# BigTime.net
KiCad netlist of a schematic drawn in EAGLE
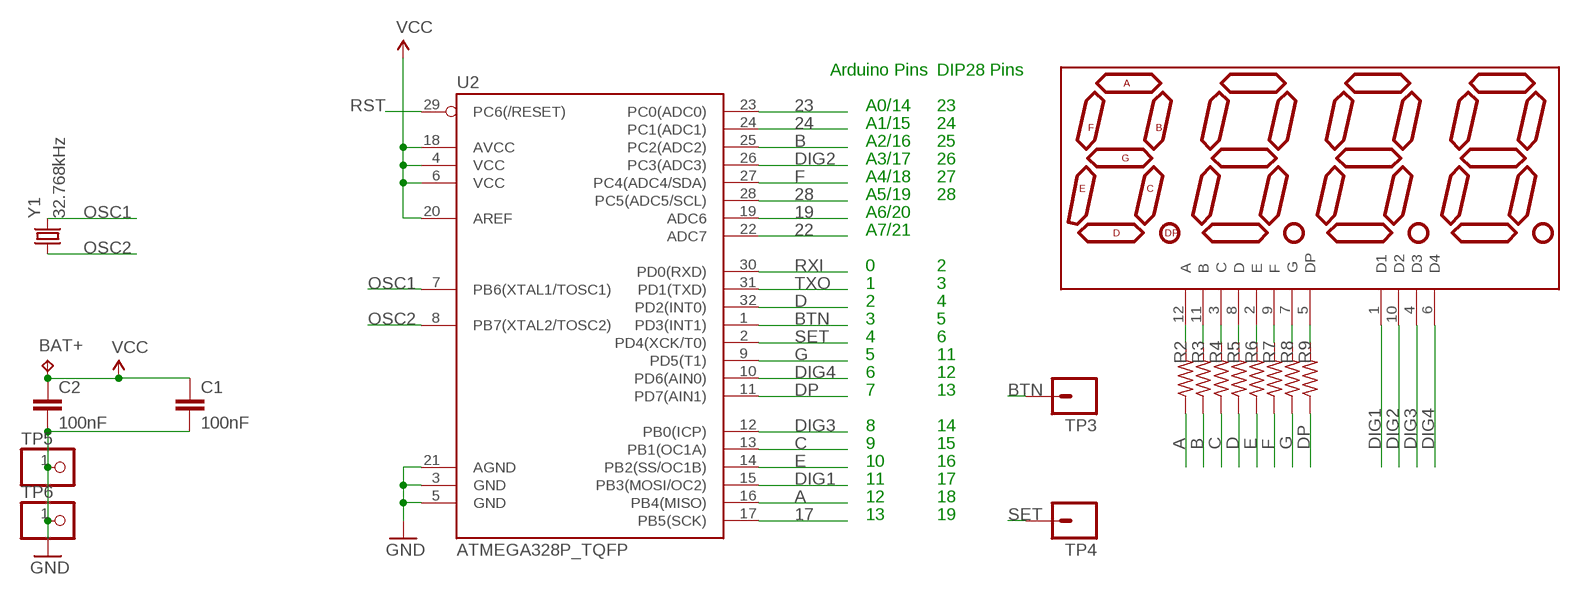
[diagram p0: schematic, sheet 1]

(export (version "E")
  (design (tool "Eeschema 10.0.6"))
  (components
    (comp (ref "BAT+")
      (value "TPTP20R")
      (footprint "eagle-import:TP20R")
      (libsource (lib "eagle-import") (part "TPTP20R"))
    )
    (comp (ref "C1")
      (value "100nF")
      (footprint "eagle-import:C0805")
      (libsource (lib "eagle-import") (part "C-EUC0805"))
    )
    (comp (ref "C2")
      (value "100nF")
      (footprint "eagle-import:C0805")
      (libsource (lib "eagle-import") (part "C-EUC0805"))
    )
    (comp (ref "DISP1")
      (value "7-SEGMENT-4DIGIT-COUNTER-HP-BUBBLE-SM")
      (footprint "eagle-import:DIL12_SM")
      (libsource (lib "eagle-import") (part "7-SEGMENT-4DIGIT-COUNTER-HP-BUBBLE-SM"))
    )
    (comp (ref "R2")
      (value "330")
      (footprint "eagle-import:R0805")
      (libsource (lib "eagle-import") (part "R-US_R0805"))
    )
    (comp (ref "R3")
      (value "330")
      (footprint "eagle-import:R0805")
      (libsource (lib "eagle-import") (part "R-US_R0805"))
    )
    (comp (ref "R4")
      (value "330")
      (footprint "eagle-import:R0805")
      (libsource (lib "eagle-import") (part "R-US_R0805"))
    )
    (comp (ref "R5")
      (value "330")
      (footprint "eagle-import:R0805")
      (libsource (lib "eagle-import") (part "R-US_R0805"))
    )
    (comp (ref "R6")
      (value "330")
      (footprint "eagle-import:R0805")
      (libsource (lib "eagle-import") (part "R-US_R0805"))
    )
    (comp (ref "R7")
      (value "330")
      (footprint "eagle-import:R0805")
      (libsource (lib "eagle-import") (part "R-US_R0805"))
    )
    (comp (ref "R8")
      (value "330")
      (footprint "eagle-import:R0805")
      (libsource (lib "eagle-import") (part "R-US_R0805"))
    )
    (comp (ref "R9")
      (value "330")
      (footprint "eagle-import:R0805")
      (libsource (lib "eagle-import") (part "R-US_R0805"))
    )
    (comp (ref "TP3")
      (value "M01EDGE_CONTACT")
      (footprint "eagle-import:WATCHBTN")
      (libsource (lib "eagle-import") (part "M01EDGE_CONTACT"))
    )
    (comp (ref "TP4")
      (value "M01EDGE_CONTACT")
      (footprint "eagle-import:WATCHBTN")
      (libsource (lib "eagle-import") (part "M01EDGE_CONTACT"))
    )
    (comp (ref "TP5")
      (value "PINHD-1X1CB")
      (footprint "eagle-import:1X01-CLEANBIG")
      (libsource (lib "eagle-import") (part "PINHD-1X1CB"))
    )
    (comp (ref "TP6")
      (value "PINHD-1X1CB")
      (footprint "eagle-import:1X01-CLEANBIG")
      (libsource (lib "eagle-import") (part "PINHD-1X1CB"))
    )
    (comp (ref "U2")
      (value "ATMEGA328P_TQFP")
      (footprint "eagle-import:TQFP32-08")
      (libsource (lib "eagle-import") (part "ATMEGA328P_TQFP"))
    )
    (comp (ref "Y1")
      (value "32.768kHz")
      (footprint "eagle-import:TC26H")
      (libsource (lib "eagle-import") (part "CRYSTALTC26H"))
    )
  )
  (nets
    (net (code "1") (name "/17") (class "Default")
      (node (ref "U2") (pin "17") (pinfunction "PB5(SCK)_17") (pintype "bidirectional"))
    )
    (net (code "2") (name "/19") (class "Default")
      (node (ref "U2") (pin "19") (pinfunction "ADC6_19") (pintype "bidirectional"))
    )
    (net (code "3") (name "/22") (class "Default")
      (node (ref "U2") (pin "22") (pinfunction "ADC7_22") (pintype "bidirectional"))
    )
    (net (code "4") (name "/23") (class "Default")
      (node (ref "U2") (pin "23") (pinfunction "PC0(ADC0)_23") (pintype "bidirectional"))
    )
    (net (code "5") (name "/24") (class "Default")
      (node (ref "U2") (pin "24") (pinfunction "PC1(ADC1)_24") (pintype "bidirectional"))
    )
    (net (code "6") (name "/28") (class "Default")
      (node (ref "U2") (pin "28") (pinfunction "PC5(ADC5/SCL)_28") (pintype "bidirectional"))
    )
    (net (code "7") (name "/A") (class "Default")
      (node (ref "R2") (pin "1") (pinfunction "1_1") (pintype "passive"))
      (node (ref "U2") (pin "16") (pinfunction "PB4(MISO)_16") (pintype "bidirectional"))
    )
    (net (code "8") (name "/B") (class "Default")
      (node (ref "R3") (pin "1") (pinfunction "1_1") (pintype "passive"))
      (node (ref "U2") (pin "25") (pinfunction "PC2(ADC2)_25") (pintype "bidirectional"))
    )
    (net (code "9") (name "/BTN") (class "Default")
      (node (ref "TP3") (pin "1") (pinfunction "1_1") (pintype "passive"))
      (node (ref "U2") (pin "1") (pinfunction "PD3(INT1)_1") (pintype "bidirectional"))
    )
    (net (code "10") (name "/C") (class "Default")
      (node (ref "R4") (pin "1") (pinfunction "1_1") (pintype "passive"))
      (node (ref "U2") (pin "13") (pinfunction "PB1(OC1A)_13") (pintype "bidirectional"))
    )
    (net (code "11") (name "/D") (class "Default")
      (node (ref "R5") (pin "1") (pinfunction "1_1") (pintype "passive"))
      (node (ref "U2") (pin "32") (pinfunction "PD2(INT0)_32") (pintype "bidirectional"))
    )
    (net (code "12") (name "/DIG1") (class "Default")
      (node (ref "DISP1") (pin "1") (pinfunction "D1_1") (pintype "bidirectional"))
      (node (ref "U2") (pin "15") (pinfunction "PB3(MOSI/OC2)_15") (pintype "bidirectional"))
    )
    (net (code "13") (name "/DIG2") (class "Default")
      (node (ref "DISP1") (pin "10") (pinfunction "D2_10") (pintype "bidirectional"))
      (node (ref "U2") (pin "26") (pinfunction "PC3(ADC3)_26") (pintype "bidirectional"))
    )
    (net (code "14") (name "/DIG3") (class "Default")
      (node (ref "DISP1") (pin "4") (pinfunction "D3_4") (pintype "bidirectional"))
      (node (ref "U2") (pin "12") (pinfunction "PB0(ICP)_12") (pintype "bidirectional"))
    )
    (net (code "15") (name "/DIG4") (class "Default")
      (node (ref "DISP1") (pin "6") (pinfunction "D4_6") (pintype "bidirectional"))
      (node (ref "U2") (pin "10") (pinfunction "PD6(AIN0)_10") (pintype "bidirectional"))
    )
    (net (code "16") (name "/DP") (class "Default")
      (node (ref "R9") (pin "1") (pinfunction "1_1") (pintype "passive"))
      (node (ref "U2") (pin "11") (pinfunction "PD7(AIN1)_11") (pintype "bidirectional"))
    )
    (net (code "17") (name "/E") (class "Default")
      (node (ref "R6") (pin "1") (pinfunction "1_1") (pintype "passive"))
      (node (ref "U2") (pin "14") (pinfunction "PB2(SS/OC1B)_14") (pintype "bidirectional"))
    )
    (net (code "18") (name "/F") (class "Default")
      (node (ref "R7") (pin "1") (pinfunction "1_1") (pintype "passive"))
      (node (ref "U2") (pin "27") (pinfunction "PC4(ADC4/SDA)_27") (pintype "bidirectional"))
    )
    (net (code "19") (name "/G") (class "Default")
      (node (ref "R8") (pin "1") (pinfunction "1_1") (pintype "passive"))
      (node (ref "U2") (pin "9") (pinfunction "PD5(T1)_9") (pintype "bidirectional"))
    )
    (net (code "20") (name "/OSC1") (class "Default")
      (node (ref "U2") (pin "7") (pinfunction "PB6(XTAL1/TOSC1)_7") (pintype "bidirectional"))
      (node (ref "Y1") (pin "2") (pinfunction "2_2") (pintype "passive"))
    )
    (net (code "21") (name "/OSC2") (class "Default")
      (node (ref "U2") (pin "8") (pinfunction "PB7(XTAL2/TOSC2)_8") (pintype "bidirectional"))
      (node (ref "Y1") (pin "1") (pinfunction "1_1") (pintype "passive"))
    )
    (net (code "22") (name "/RST") (class "Default")
      (node (ref "U2") (pin "29") (pinfunction "PC6(/RESET)_29") (pintype "bidirectional"))
    )
    (net (code "23") (name "/RXI") (class "Default")
      (node (ref "U2") (pin "30") (pinfunction "PD0(RXD)_30") (pintype "bidirectional"))
    )
    (net (code "24") (name "/SET") (class "Default")
      (node (ref "TP4") (pin "1") (pinfunction "1_1") (pintype "passive"))
      (node (ref "U2") (pin "2") (pinfunction "PD4(XCK/T0)_2") (pintype "bidirectional"))
    )
    (net (code "25") (name "/TXO") (class "Default")
      (node (ref "U2") (pin "31") (pinfunction "PD1(TXD)_31") (pintype "bidirectional"))
    )
    (net (code "26") (name "GND") (class "Default")
      (node (ref "C1") (pin "2") (pinfunction "2_2") (pintype "passive"))
      (node (ref "C2") (pin "2") (pinfunction "2_2") (pintype "passive"))
      (node (ref "TP5") (pin "1") (pinfunction "1_1") (pintype "passive"))
      (node (ref "TP6") (pin "1") (pinfunction "1_1") (pintype "passive"))
      (node (ref "U2") (pin "21") (pinfunction "AGND_21") (pintype "bidirectional"))
      (node (ref "U2") (pin "3") (pinfunction "GND_3") (pintype "bidirectional"))
      (node (ref "U2") (pin "5") (pinfunction "GND_5") (pintype "bidirectional"))
    )
    (net (code "27") (name "Net-(DISP1-A)") (class "Default")
      (node (ref "DISP1") (pin "12") (pinfunction "A_12") (pintype "bidirectional"))
      (node (ref "R2") (pin "2") (pinfunction "2_2") (pintype "passive"))
    )
    (net (code "28") (name "Net-(DISP1-B)") (class "Default")
      (node (ref "DISP1") (pin "11") (pinfunction "B_11") (pintype "bidirectional"))
      (node (ref "R3") (pin "2") (pinfunction "2_2") (pintype "passive"))
    )
    (net (code "29") (name "Net-(DISP1-C)") (class "Default")
      (node (ref "DISP1") (pin "3") (pinfunction "C_3") (pintype "bidirectional"))
      (node (ref "R4") (pin "2") (pinfunction "2_2") (pintype "passive"))
    )
    (net (code "30") (name "Net-(DISP1-D)") (class "Default")
      (node (ref "DISP1") (pin "8") (pinfunction "D_8") (pintype "bidirectional"))
      (node (ref "R5") (pin "2") (pinfunction "2_2") (pintype "passive"))
    )
    (net (code "31") (name "Net-(DISP1-DP)") (class "Default")
      (node (ref "DISP1") (pin "5") (pinfunction "DP_5") (pintype "bidirectional"))
      (node (ref "R9") (pin "2") (pinfunction "2_2") (pintype "passive"))
    )
    (net (code "32") (name "Net-(DISP1-E)") (class "Default")
      (node (ref "DISP1") (pin "2") (pinfunction "E_2") (pintype "bidirectional"))
      (node (ref "R6") (pin "2") (pinfunction "2_2") (pintype "passive"))
    )
    (net (code "33") (name "Net-(DISP1-F)") (class "Default")
      (node (ref "DISP1") (pin "9") (pinfunction "F_9") (pintype "bidirectional"))
      (node (ref "R7") (pin "2") (pinfunction "2_2") (pintype "passive"))
    )
    (net (code "34") (name "Net-(DISP1-G)") (class "Default")
      (node (ref "DISP1") (pin "7") (pinfunction "G_7") (pintype "bidirectional"))
      (node (ref "R8") (pin "2") (pinfunction "2_2") (pintype "passive"))
    )
    (net (code "35") (name "VCC") (class "Default")
      (node (ref "BAT+") (pin "TP") (pinfunction "TP_TP") (pintype "input"))
      (node (ref "C1") (pin "1") (pinfunction "1_1") (pintype "passive"))
      (node (ref "C2") (pin "1") (pinfunction "1_1") (pintype "passive"))
      (node (ref "U2") (pin "18") (pinfunction "AVCC_18") (pintype "bidirectional"))
      (node (ref "U2") (pin "20") (pinfunction "AREF_20") (pintype "bidirectional"))
      (node (ref "U2") (pin "4") (pinfunction "VCC_4") (pintype "bidirectional"))
      (node (ref "U2") (pin "6") (pinfunction "VCC_6") (pintype "bidirectional"))
    )
  )
)
